# mcu.net
KiCad netlist of a schematic drawn in Altium Designer
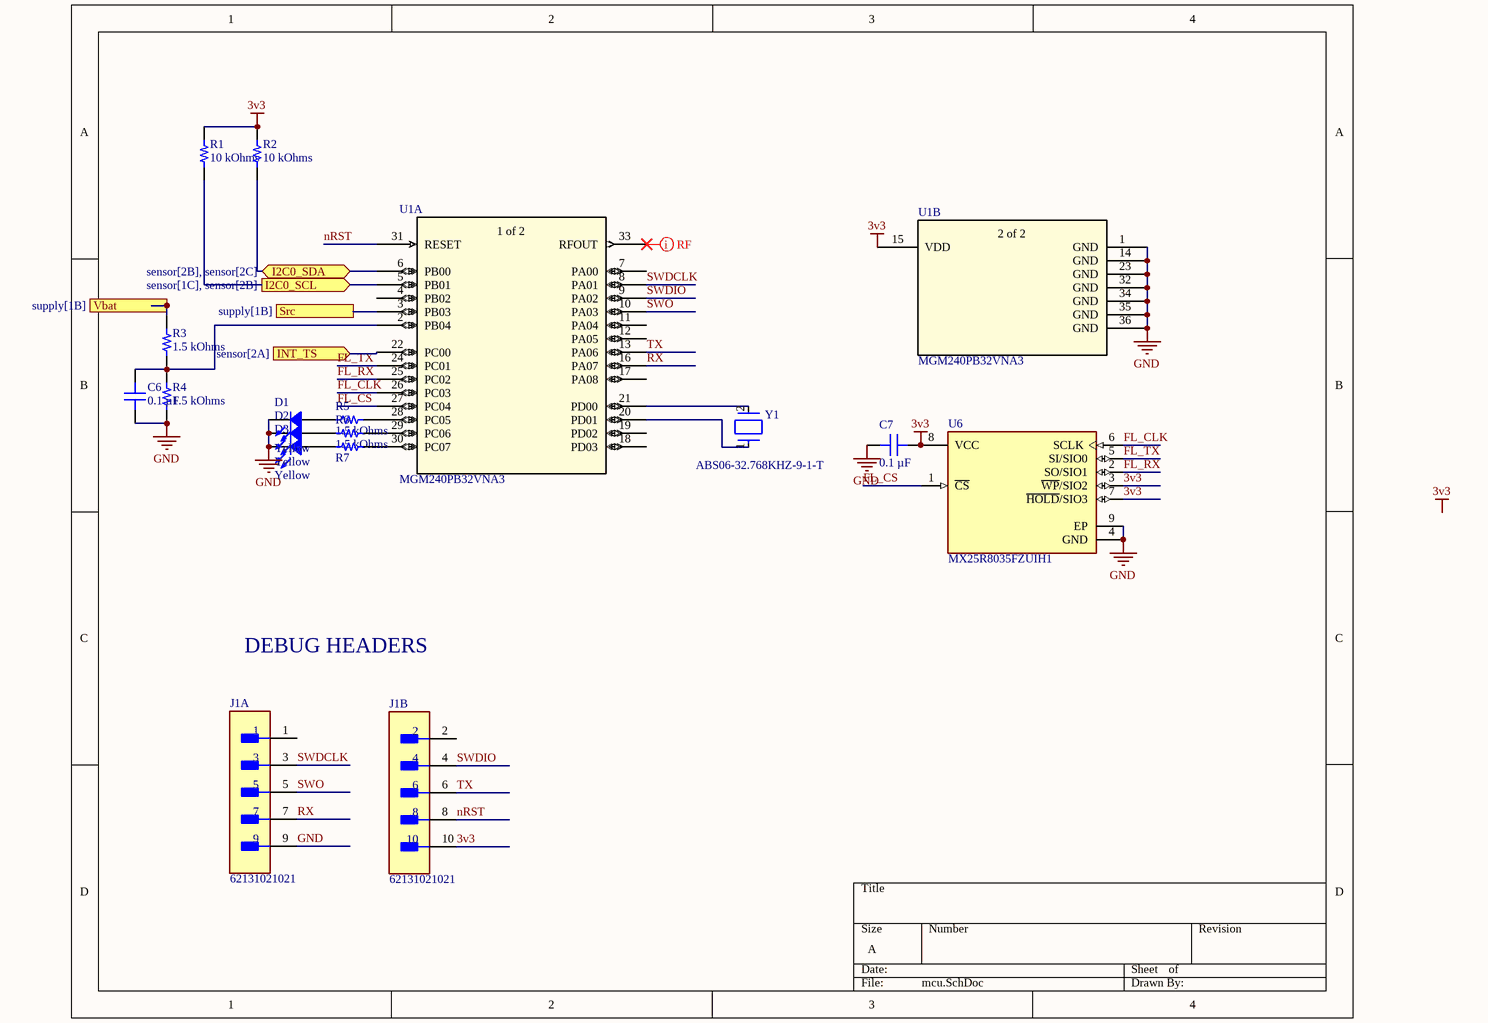
[diagram p0: mcu.SchDoc]

(export (version "E")
  (design (tool "Eeschema 10.0.6"))
  (components
    (comp (ref "C6")
      (value "0.1 µF")
      (footprint "CAP 0402_1005")
      (description "CAP CER 0.1UF 4V X5R 0402")
      (fields (field (name "PART NUMBER") "C0402C104K7PAC7867") (field (name "MANUFACTURER") "KEMET"))
      (libsource (lib "Celestial Altium Library - altium_library") (part "Capacitor"))
    )
    (comp (ref "C7")
      (value "0.1 µF")
      (footprint "CAP 0402_1005")
      (description "CAP CER 0.1UF 4V X5R 0402")
      (fields (field (name "PART NUMBER") "C0402C104K7PAC7867") (field (name "MANUFACTURER") "KEMET"))
      (libsource (lib "Celestial Altium Library - altium_library") (part "Capacitor"))
    )
    (comp (ref "D1")
      (value "Yellow")
      (footprint "LED 0402_1005 YELLOW")
      (description "0402 YELLOW")
      (fields
        (field (name "PART NUMBER") "BL-HKC37A-AV-TRB")
        (field (name "MANUFACTURER") "American Bright Optoelectronics Corporation")
      )
      (libsource (lib "Celestial Altium Library - altium_library") (part "LED"))
    )
    (comp (ref "D2")
      (value "Yellow")
      (footprint "LED 0402_1005 YELLOW")
      (description "0402 YELLOW")
      (fields
        (field (name "PART NUMBER") "BL-HKC37A-AV-TRB")
        (field (name "MANUFACTURER") "American Bright Optoelectronics Corporation")
      )
      (libsource (lib "Celestial Altium Library - altium_library") (part "LED"))
    )
    (comp (ref "D3")
      (value "Yellow")
      (footprint "LED 0402_1005 YELLOW")
      (description "0402 YELLOW")
      (fields
        (field (name "PART NUMBER") "BL-HKC37A-AV-TRB")
        (field (name "MANUFACTURER") "American Bright Optoelectronics Corporation")
      )
      (libsource (lib "Celestial Altium Library - altium_library") (part "LED"))
    )
    (comp (ref "J1")
      (value "62131021021")
      (footprint "FP-62131021021-MFG")
      (description "1.27mm SMT Straight Dual Pin Header WR-PHD")
      (libsource (lib "Altium Content Vault") (part "aca50b2a6b2128cc4a58f514acdea57"))
    )
    (comp (ref "R1")
      (value "10 kOhms")
      (footprint "RES 0402_1005")
      (description "RES 1.5K OHM 0.05% 1/10W 0402")
      (fields
        (field (name "PART NUMBER") "ERA-2VRW1501X")
        (field (name "MANUFACTURER") "Panasonic Electronic Components")
      )
      (libsource (lib "Celestial Altium Library - altium_library") (part "Resistor"))
    )
    (comp (ref "R2")
      (value "10 kOhms")
      (footprint "RES 0402_1005")
      (description "RES 1.5K OHM 0.05% 1/10W 0402")
      (fields
        (field (name "PART NUMBER") "ERA-2VRW1501X")
        (field (name "MANUFACTURER") "Panasonic Electronic Components")
      )
      (libsource (lib "Celestial Altium Library - altium_library") (part "Resistor"))
    )
    (comp (ref "R3")
      (value "1.5 kOhms")
      (footprint "RES 0402_1005")
      (description "RES 1.5K OHM 0.05% 1/10W 0402")
      (fields
        (field (name "PART NUMBER") "ERA-2VRW1501X")
        (field (name "MANUFACTURER") "Panasonic Electronic Components")
      )
      (libsource (lib "Celestial Altium Library - altium_library") (part "Resistor"))
    )
    (comp (ref "R4")
      (value "1.5 kOhms")
      (footprint "RES 0402_1005")
      (description "RES 1.5K OHM 0.05% 1/10W 0402")
      (fields
        (field (name "PART NUMBER") "ERA-2VRW1501X")
        (field (name "MANUFACTURER") "Panasonic Electronic Components")
      )
      (libsource (lib "Celestial Altium Library - altium_library") (part "Resistor"))
    )
    (comp (ref "R5")
      (value "1.5 kOhms")
      (footprint "RES 0402_1005")
      (description "RES 1.5K OHM 0.05% 1/10W 0402")
      (fields
        (field (name "PART NUMBER") "ERA-2VRW1501X")
        (field (name "MANUFACTURER") "Panasonic Electronic Components")
      )
      (libsource (lib "Celestial Altium Library - altium_library") (part "Resistor"))
    )
    (comp (ref "R6")
      (value "1.5 kOhms")
      (footprint "RES 0402_1005")
      (description "RES 1.5K OHM 0.05% 1/10W 0402")
      (fields
        (field (name "PART NUMBER") "ERA-2VRW1501X")
        (field (name "MANUFACTURER") "Panasonic Electronic Components")
      )
      (libsource (lib "Celestial Altium Library - altium_library") (part "Resistor"))
    )
    (comp (ref "R7")
      (value "~")
      (footprint "RES 0402_1005")
      (description "RES 1.5K OHM 0.05% 1/10W 0402")
      (fields
        (field (name "PART NUMBER") "ERA-2VRW1501X")
        (field (name "MANUFACTURER") "Panasonic Electronic Components")
      )
      (libsource (lib "Celestial Altium Library - altium_library") (part "Resistor"))
    )
    (comp (ref "U1")
      (value "MGM240PB32VNA3")
      (footprint "xGM240P")
      (description "No Description Available")
      (libsource (lib "MGM240PB32VNA3") (part "MGM240PB32VNA3"))
    )
    (comp (ref "U6")
      (value "MX25R8035FZUIH1")
      (footprint "FP-USON-8-2x3mm-MFG")
      (description "IC FLASH 8M SPI 108MHZ 8USON")
      (libsource (lib "Altium Content Vault") (part "ffc21d3be60da27da01f02837e715d7"))
    )
    (comp (ref "Y1")
      (value "ABS06-32.768KHZ-9-1-T")
      (footprint "FP-ABS06-MFG")
      (description "Crystal 32.768kHz ±10ppm (Tol) 9pF FUND 90kΩ 2-Pin Mini-CSMD T/R")
      (fields (field (name "TOLERANCE") "10ppm"))
      (libsource (lib "Altium Content Vault") (part "c23a69dc6c9e2f18f2079038eb95dd1"))
    )
  )
  (nets
    (net (code "1") (name "/FL_CLK") (class "Default")
      (node (ref "U1") (pin "26") (pinfunction "PC03_26") (pintype "bidirectional"))
      (node (ref "U6") (pin "6") (pinfunction "SCLK_6") (pintype "input"))
    )
    (net (code "2") (name "/FL_CS") (class "Default")
      (node (ref "U1") (pin "27") (pinfunction "PC04_27") (pintype "bidirectional"))
      (node (ref "U6") (pin "1") (pinfunction "~{CS}_1") (pintype "input"))
    )
    (net (code "3") (name "/FL_RX") (class "Default")
      (node (ref "U1") (pin "25") (pinfunction "PC02_25") (pintype "bidirectional"))
      (node (ref "U6") (pin "2") (pinfunction "SO/SIO1_2") (pintype "bidirectional"))
    )
    (net (code "4") (name "/FL_TX") (class "Default")
      (node (ref "U1") (pin "24") (pinfunction "PC01_24") (pintype "bidirectional"))
      (node (ref "U6") (pin "5") (pinfunction "SI/SIO0_5") (pintype "bidirectional"))
    )
    (net (code "5") (name "/I2C0_SCL") (class "Default")
      (node (ref "R1") (pin "2") (pinfunction "2_2") (pintype "passive"))
      (node (ref "U1") (pin "5") (pinfunction "PB01_5") (pintype "bidirectional"))
    )
    (net (code "6") (name "/I2C0_SDA") (class "Default")
      (node (ref "R2") (pin "2") (pinfunction "2_2") (pintype "passive"))
      (node (ref "U1") (pin "6") (pinfunction "PB00_6") (pintype "bidirectional"))
    )
    (net (code "7") (name "/INT_TS") (class "Default")
      (node (ref "U1") (pin "22") (pinfunction "PC00_22") (pintype "bidirectional"))
    )
    (net (code "8") (name "/RX") (class "Default")
      (node (ref "J1") (pin "7") (pinfunction "7_7") (pintype "passive"))
      (node (ref "U1") (pin "16") (pinfunction "PA07_16") (pintype "bidirectional"))
    )
    (net (code "9") (name "/SWDCLK") (class "Default")
      (node (ref "J1") (pin "3") (pinfunction "3_3") (pintype "passive"))
      (node (ref "U1") (pin "8") (pinfunction "PA01_8") (pintype "bidirectional"))
    )
    (net (code "10") (name "/SWDIO") (class "Default")
      (node (ref "J1") (pin "4") (pinfunction "4_4") (pintype "passive"))
      (node (ref "U1") (pin "9") (pinfunction "PA02_9") (pintype "bidirectional"))
    )
    (net (code "11") (name "/SWO") (class "Default")
      (node (ref "J1") (pin "5") (pinfunction "5_5") (pintype "passive"))
      (node (ref "U1") (pin "10") (pinfunction "PA03_10") (pintype "bidirectional"))
    )
    (net (code "12") (name "/Src") (class "Default")
      (node (ref "U1") (pin "3") (pinfunction "PB03_3") (pintype "bidirectional"))
    )
    (net (code "13") (name "/TX") (class "Default")
      (node (ref "J1") (pin "6") (pinfunction "6_6") (pintype "passive"))
      (node (ref "U1") (pin "13") (pinfunction "PA06_13") (pintype "bidirectional"))
    )
    (net (code "14") (name "/Vbat") (class "Default")
      (node (ref "R3") (pin "1") (pinfunction "1_1") (pintype "passive"))
    )
    (net (code "15") (name "/nRST") (class "Default")
      (node (ref "J1") (pin "8") (pinfunction "8_8") (pintype "passive"))
      (node (ref "U1") (pin "31") (pinfunction "RESET_31") (pintype "input"))
    )
    (net (code "16") (name "3v3") (class "Default")
      (node (ref "C7") (pin "1") (pinfunction "1_1") (pintype "passive"))
      (node (ref "J1") (pin "10") (pinfunction "10_10") (pintype "passive"))
      (node (ref "R1") (pin "1") (pinfunction "1_1") (pintype "passive"))
      (node (ref "R2") (pin "1") (pinfunction "1_1") (pintype "passive"))
      (node (ref "U1") (pin "15") (pinfunction "VDD_15") (pintype "power_in"))
      (node (ref "U6") (pin "3") (pinfunction "~{WP}/SIO2_3") (pintype "bidirectional"))
      (node (ref "U6") (pin "7") (pinfunction "~{HOLD}/SIO3_7") (pintype "bidirectional"))
      (node (ref "U6") (pin "8") (pinfunction "VCC_8") (pintype "power_in"))
    )
    (net (code "17") (name "GND") (class "Default")
      (node (ref "C6") (pin "1") (pinfunction "1_1") (pintype "passive"))
      (node (ref "C7") (pin "2") (pinfunction "2_2") (pintype "passive"))
      (node (ref "D1") (pin "2") (pinfunction "2_2") (pintype "passive"))
      (node (ref "D2") (pin "2") (pinfunction "2_2") (pintype "passive"))
      (node (ref "D3") (pin "2") (pinfunction "2_2") (pintype "passive"))
      (node (ref "J1") (pin "9") (pinfunction "9_9") (pintype "passive"))
      (node (ref "R4") (pin "2") (pinfunction "2_2") (pintype "passive"))
      (node (ref "U1") (pin "1") (pinfunction "GND_1") (pintype "power_in"))
      (node (ref "U1") (pin "14") (pinfunction "GND_14") (pintype "power_in"))
      (node (ref "U1") (pin "23") (pinfunction "GND_23") (pintype "power_in"))
      (node (ref "U1") (pin "32") (pinfunction "GND_32") (pintype "power_in"))
      (node (ref "U1") (pin "34") (pinfunction "GND_34") (pintype "power_in"))
      (node (ref "U1") (pin "35") (pinfunction "GND_35") (pintype "power_in"))
      (node (ref "U1") (pin "36") (pinfunction "GND_36") (pintype "power_in"))
      (node (ref "U6") (pin "4") (pinfunction "GND_4") (pintype "power_in"))
      (node (ref "U6") (pin "9") (pinfunction "EP_9") (pintype "passive"))
    )
    (net (code "18") (name "Net-(D1-Pad1)") (class "Default")
      (node (ref "D1") (pin "1") (pinfunction "1_1") (pintype "passive"))
      (node (ref "R5") (pin "1") (pinfunction "1_1") (pintype "passive"))
    )
    (net (code "19") (name "Net-(D2-Pad1)") (class "Default")
      (node (ref "D2") (pin "1") (pinfunction "1_1") (pintype "passive"))
      (node (ref "R6") (pin "1") (pinfunction "1_1") (pintype "passive"))
    )
    (net (code "20") (name "Net-(D3-Pad1)") (class "Default")
      (node (ref "D3") (pin "1") (pinfunction "1_1") (pintype "passive"))
      (node (ref "R7") (pin "1") (pinfunction "1_1") (pintype "passive"))
    )
    (net (code "21") (name "Net-(U1A-PB04)") (class "Default")
      (node (ref "C6") (pin "2") (pinfunction "2_2") (pintype "passive"))
      (node (ref "R3") (pin "2") (pinfunction "2_2") (pintype "passive"))
      (node (ref "R4") (pin "1") (pinfunction "1_1") (pintype "passive"))
      (node (ref "U1") (pin "2") (pinfunction "PB04_2") (pintype "bidirectional"))
    )
    (net (code "22") (name "Net-(U1A-PC05)") (class "Default")
      (node (ref "R5") (pin "2") (pinfunction "2_2") (pintype "passive"))
      (node (ref "U1") (pin "28") (pinfunction "PC05_28") (pintype "bidirectional"))
    )
    (net (code "23") (name "Net-(U1A-PC06)") (class "Default")
      (node (ref "R6") (pin "2") (pinfunction "2_2") (pintype "passive"))
      (node (ref "U1") (pin "29") (pinfunction "PC06_29") (pintype "bidirectional"))
    )
    (net (code "24") (name "Net-(U1A-PC07)") (class "Default")
      (node (ref "R7") (pin "2") (pinfunction "2_2") (pintype "passive"))
      (node (ref "U1") (pin "30") (pinfunction "PC07_30") (pintype "bidirectional"))
    )
    (net (code "25") (name "Net-(U1A-PD00)") (class "Default")
      (node (ref "U1") (pin "21") (pinfunction "PD00_21") (pintype "bidirectional"))
      (node (ref "Y1") (pin "2") (pinfunction "2_2") (pintype "passive"))
    )
    (net (code "26") (name "Net-(U1A-PD01)") (class "Default")
      (node (ref "U1") (pin "20") (pinfunction "PD01_20") (pintype "bidirectional"))
      (node (ref "Y1") (pin "1") (pinfunction "1_1") (pintype "passive"))
    )
    (net (code "27") (name "unconnected-(J1-Pad1)") (class "Default")
      (node (ref "J1") (pin "1") (pinfunction "1_1") (pintype "passive"))
    )
    (net (code "28") (name "unconnected-(J1-Pad2)") (class "Default")
      (node (ref "J1") (pin "2") (pinfunction "2_2") (pintype "passive"))
    )
    (net (code "29") (name "unconnected-(U1A-PA00-Pad7)") (class "Default")
      (node (ref "U1") (pin "7") (pinfunction "PA00_7") (pintype "bidirectional"))
    )
    (net (code "30") (name "unconnected-(U1A-PA04-Pad11)") (class "Default")
      (node (ref "U1") (pin "11") (pinfunction "PA04_11") (pintype "bidirectional"))
    )
    (net (code "31") (name "unconnected-(U1A-PA05-Pad12)") (class "Default")
      (node (ref "U1") (pin "12") (pinfunction "PA05_12") (pintype "bidirectional"))
    )
    (net (code "32") (name "unconnected-(U1A-PA08-Pad17)") (class "Default")
      (node (ref "U1") (pin "17") (pinfunction "PA08_17") (pintype "bidirectional"))
    )
    (net (code "33") (name "unconnected-(U1A-PB02-Pad4)") (class "Default")
      (node (ref "U1") (pin "4") (pinfunction "PB02_4") (pintype "bidirectional"))
    )
    (net (code "34") (name "unconnected-(U1A-PD02-Pad19)") (class "Default")
      (node (ref "U1") (pin "19") (pinfunction "PD02_19") (pintype "bidirectional"))
    )
    (net (code "35") (name "unconnected-(U1A-PD03-Pad18)") (class "Default")
      (node (ref "U1") (pin "18") (pinfunction "PD03_18") (pintype "bidirectional"))
    )
    (net (code "36") (name "unconnected-(U1A-RFOUT-Pad33)") (class "Default")
      (node (ref "U1") (pin "33") (pinfunction "RFOUT_33") (pintype "output+no_connect"))
    )
  )
)
